# FPGA_PART1.net
KiCad netlist of a schematic drawn in Altium Designer
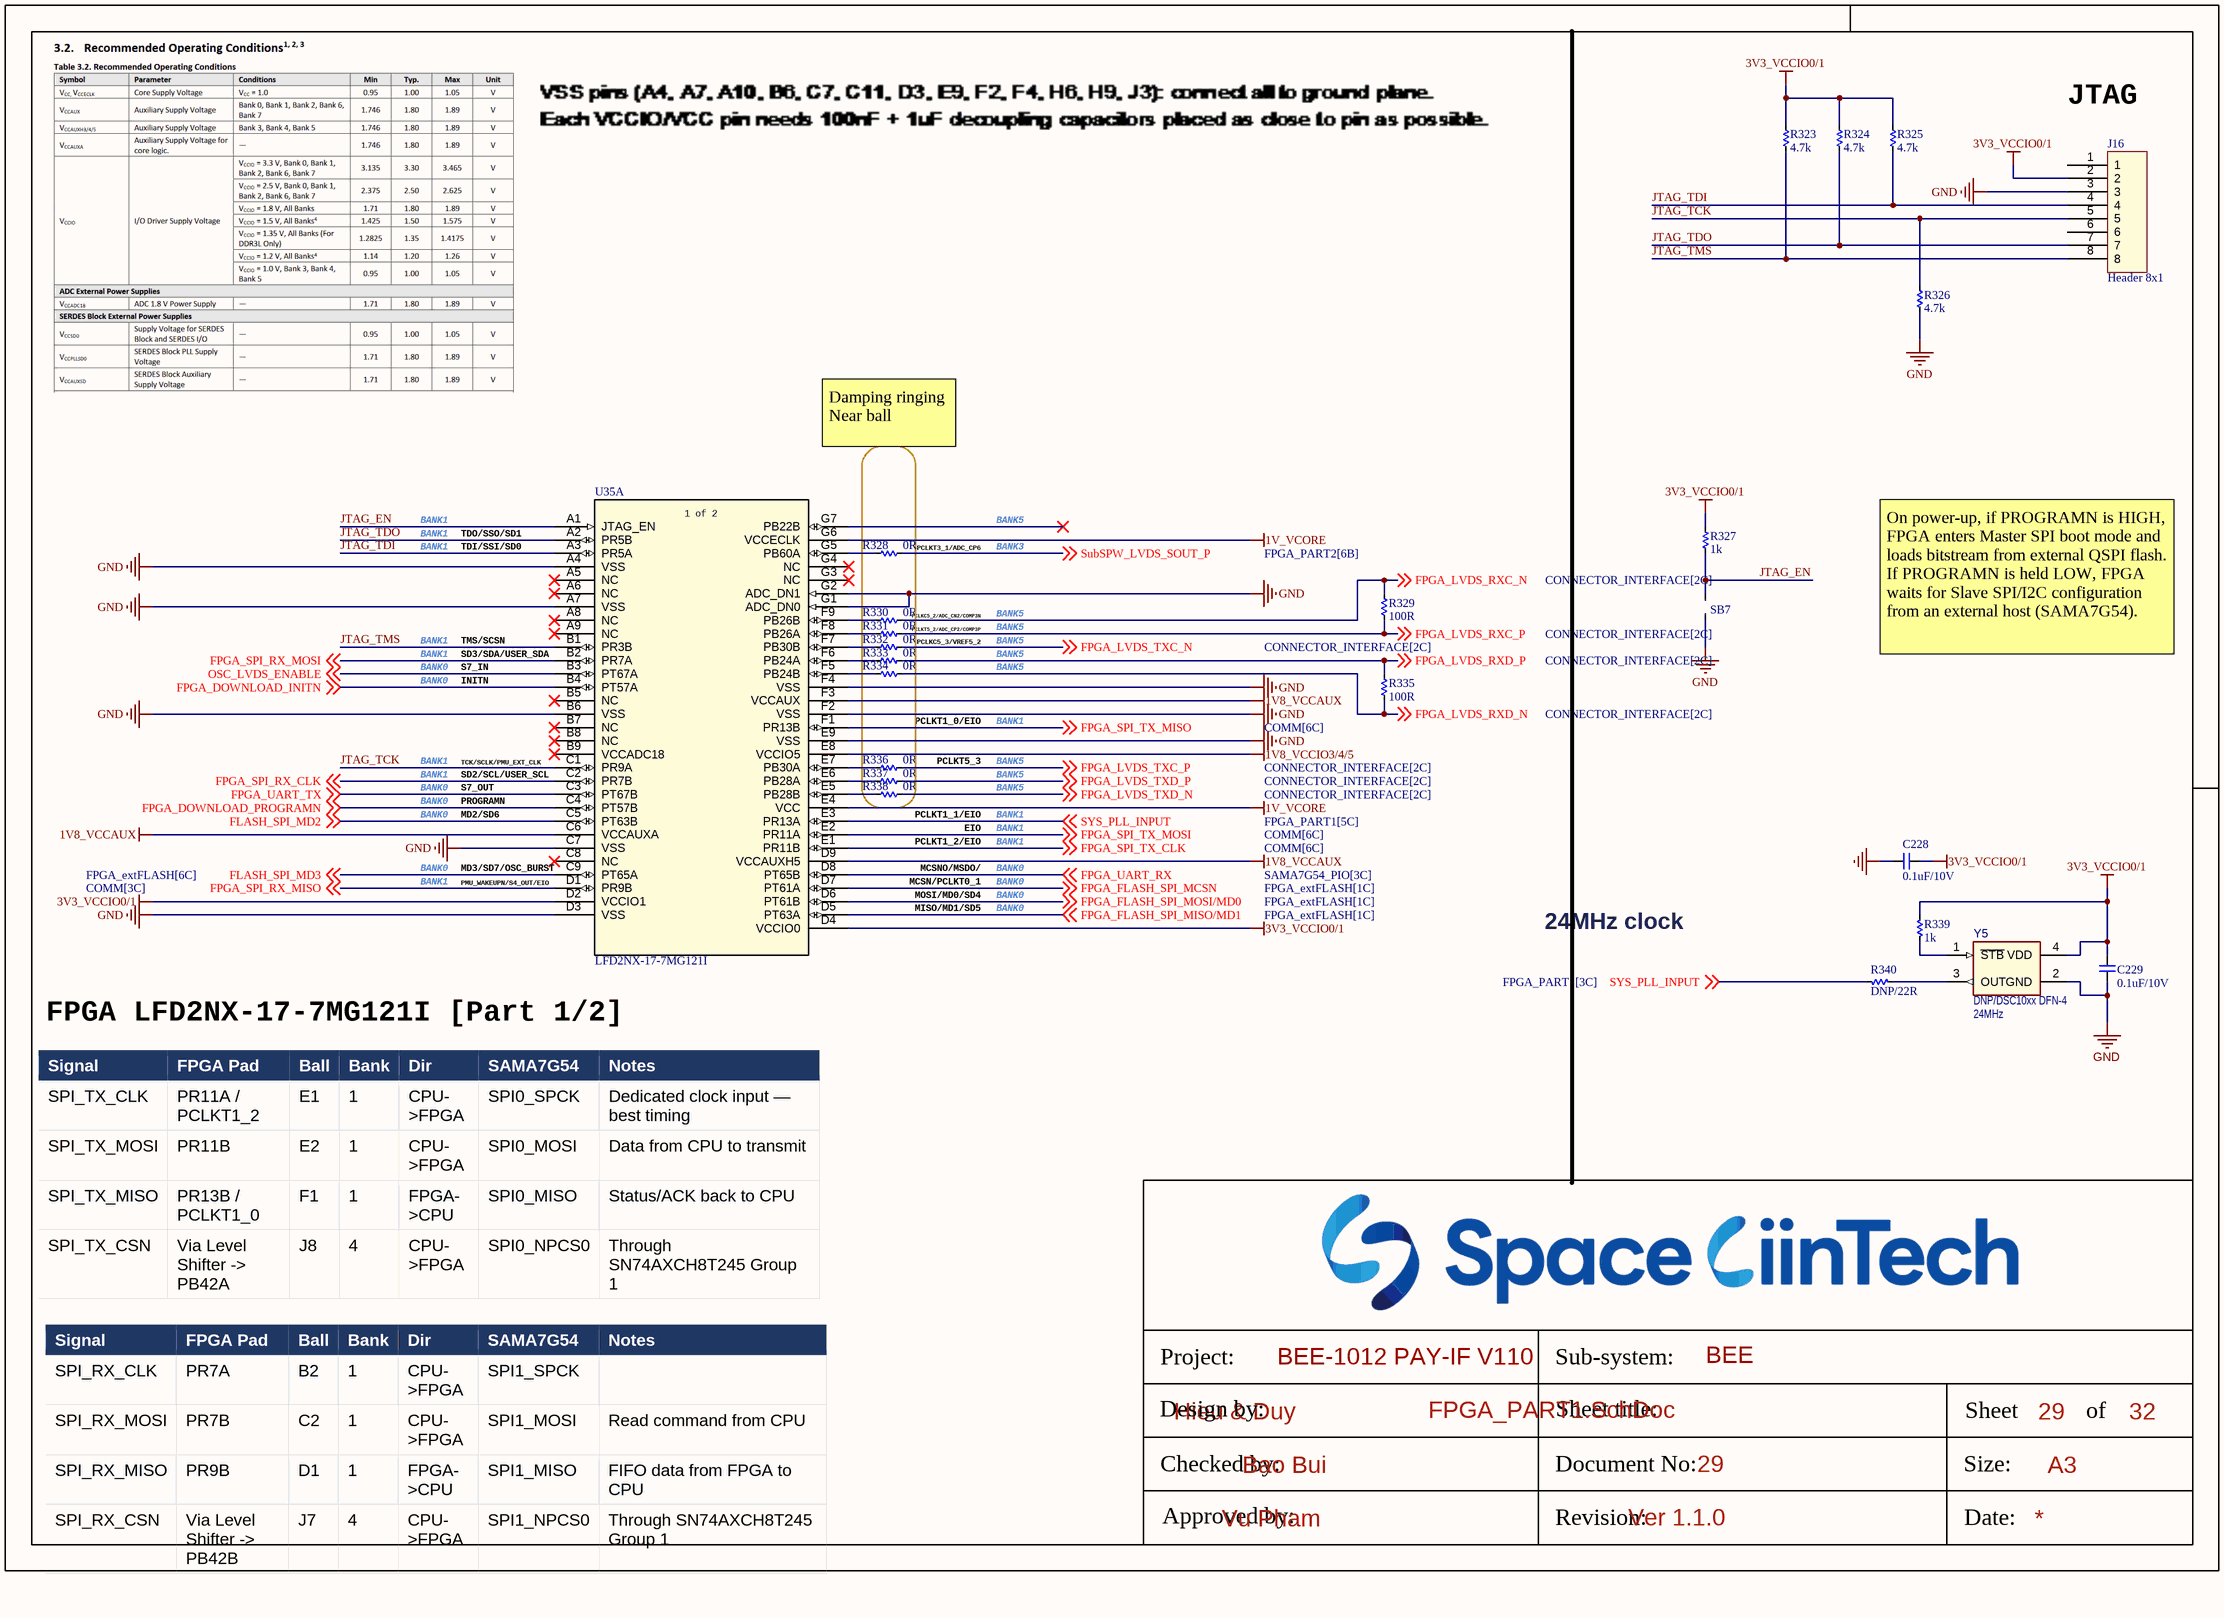
[diagram p0: FPGA_PART1.SchDoc]

(export (version "E")
  (design (tool "Eeschema 10.0.6"))
  (components
    (comp (ref "C228")
      (value "0.1uF/10V")
      (footprint "CAP_C_1005X50_L")
      (description "CAP")
      (libsource (lib "LABLIB") (part "_CAP_C_2"))
    )
    (comp (ref "C229")
      (value "0.1uF/10V")
      (footprint "CAP_C_1005X50_L")
      (description "CAP")
      (libsource (lib "LABLIB") (part "_CAP_C_2"))
    )
    (comp (ref "J16")
      (value "Header 8x1")
      (footprint "SAMTEC_TSM-108-01-L-SV-P-TR")
      (libsource (lib "LABLIB") (part "Header 8x1"))
    )
    (comp (ref "R323")
      (value "4.7k")
      (footprint "RES_C_1005x30_L")
      (description "RES")
      (libsource (lib "IFBschelib") (part "_RES_B_2"))
    )
    (comp (ref "R324")
      (value "4.7k")
      (footprint "RES_C_1005x30_L")
      (description "RES")
      (libsource (lib "IFBschelib") (part "_RES_B_2"))
    )
    (comp (ref "R325")
      (value "4.7k")
      (footprint "RES_C_1005x30_L")
      (description "RES")
      (libsource (lib "IFBschelib") (part "_RES_B_2"))
    )
    (comp (ref "R326")
      (value "4.7k")
      (footprint "RES_C_1005x30_L")
      (description "RES")
      (libsource (lib "IFBschelib") (part "_RES_B_2"))
    )
    (comp (ref "R327")
      (value "1k")
      (footprint "RES_C_1005x30_L")
      (description "RES")
      (libsource (lib "LABLIB") (part "_RES_B_2"))
    )
    (comp (ref "R328")
      (value "0R")
      (footprint "RES_C_1005x30_L")
      (description "RES")
      (libsource (lib "LABLIB") (part "_RES_B_2"))
    )
    (comp (ref "R329")
      (value "100R")
      (footprint "RES_C_1005x30_L")
      (description "RES")
      (libsource (lib "LABLIB") (part "_RES_B_2"))
    )
    (comp (ref "R330")
      (value "0R")
      (footprint "RES_C_1005x30_L")
      (description "RES")
      (libsource (lib "LABLIB") (part "_RES_B_2"))
    )
    (comp (ref "R331")
      (value "0R")
      (footprint "RES_C_1005x30_L")
      (description "RES")
      (libsource (lib "LABLIB") (part "_RES_B_2"))
    )
    (comp (ref "R332")
      (value "0R")
      (footprint "RES_C_1005x30_L")
      (description "RES")
      (libsource (lib "LABLIB") (part "_RES_B_2"))
    )
    (comp (ref "R333")
      (value "0R")
      (footprint "RES_C_1005x30_L")
      (description "RES")
      (libsource (lib "LABLIB") (part "_RES_B_2"))
    )
    (comp (ref "R334")
      (value "0R")
      (footprint "RES_C_1005x30_L")
      (description "RES")
      (libsource (lib "LABLIB") (part "_RES_B_2"))
    )
    (comp (ref "R335")
      (value "100R")
      (footprint "RES_C_1005x30_L")
      (description "RES")
      (libsource (lib "LABLIB") (part "_RES_B_2"))
    )
    (comp (ref "R336")
      (value "0R")
      (footprint "RES_C_1005x30_L")
      (description "RES")
      (libsource (lib "LABLIB") (part "_RES_B_2"))
    )
    (comp (ref "R337")
      (value "0R")
      (footprint "RES_C_1005x30_L")
      (description "RES")
      (libsource (lib "LABLIB") (part "_RES_B_2"))
    )
    (comp (ref "R338")
      (value "0R")
      (footprint "RES_C_1005x30_L")
      (description "RES")
      (libsource (lib "LABLIB") (part "_RES_B_2"))
    )
    (comp (ref "R339")
      (value "1k")
      (footprint "RES_C_1005x30_L")
      (description "RES")
      (libsource (lib "LABLIB") (part "_RES_B_2"))
    )
    (comp (ref "R340")
      (value "DNP/22R")
      (footprint "RES_C_1005x30_L")
      (description "RES")
      (libsource (lib "LABLIB") (part "_RES_B_2"))
    )
    (comp (ref "SB7")
      (value "JUMPER")
      (footprint "JUMPER_1608")
      (libsource (lib "IFBschelib") (part "JUMPER"))
    )
    (comp (ref "U35")
      (value "LFD2NX-17-7MG121I")
      (footprint "csfBGA121_LAT")
      (description "Description")
      (fields (field (name "COPYRIGHT") "Copyright (C) 2025 Ultra Librarian. All rights reserved."))
      (libsource (lib "IFBschelib_offline") (part "LFD2NX-17-7MG121I"))
    )
    (comp (ref "Y5")
      (value "DNP/DSC10xx DFN-4")
      (footprint "DFN-4_2.5x2")
      (fields (field (name "ALTIUM_VALUE") "24MHz") (field (name "OWNER") "Maurizio Gavardoni"))
      (libsource (lib "LABLIB") (part "DSC10xx DFN-4"))
    )
  )
  (nets
    (net (code "1") (name "/JTAG_EN") (class "Default")
      (node (ref "R327") (pin "1") (pinfunction "1_1") (pintype "passive"))
      (node (ref "SB7") (pin "2") (pinfunction "2_2") (pintype "passive"))
      (node (ref "U35") (pin "A1") (pinfunction "JTAG_EN_A1") (pintype "input"))
    )
    (net (code "2") (name "/JTAG_TCK") (class "Default")
      (node (ref "J16") (pin "5") (pinfunction "5_5") (pintype "passive"))
      (node (ref "R326") (pin "2") (pinfunction "2_2") (pintype "passive"))
      (node (ref "U35") (pin "C1") (pinfunction "PR9A_C1") (pintype "bidirectional"))
    )
    (net (code "3") (name "/JTAG_TDI") (class "Default")
      (node (ref "J16") (pin "4") (pinfunction "4_4") (pintype "passive"))
      (node (ref "R325") (pin "1") (pinfunction "1_1") (pintype "passive"))
      (node (ref "U35") (pin "A3") (pinfunction "PR5A_A3") (pintype "bidirectional"))
    )
    (net (code "4") (name "/JTAG_TDO") (class "Default")
      (node (ref "J16") (pin "7") (pinfunction "7_7") (pintype "passive"))
      (node (ref "R324") (pin "1") (pinfunction "1_1") (pintype "passive"))
      (node (ref "U35") (pin "A2") (pinfunction "PR5B_A2") (pintype "bidirectional"))
    )
    (net (code "5") (name "/JTAG_TMS") (class "Default")
      (node (ref "J16") (pin "8") (pinfunction "8_8") (pintype "passive"))
      (node (ref "R323") (pin "1") (pinfunction "1_1") (pintype "passive"))
      (node (ref "U35") (pin "B1") (pinfunction "PR3B_B1") (pintype "bidirectional"))
    )
    (net (code "6") (name "1V8_VCCAUX") (class "Default")
      (node (ref "U35") (pin "C6") (pinfunction "VCCAUXA_C6") (pintype "power_in"))
      (node (ref "U35") (pin "D9") (pinfunction "VCCAUXH5_D9") (pintype "power_in"))
      (node (ref "U35") (pin "F3") (pinfunction "VCCAUX_F3") (pintype "power_in"))
    )
    (net (code "7") (name "1V8_VCCIO3{slash}4{slash}5") (class "Default")
      (node (ref "U35") (pin "E8") (pinfunction "VCCIO5_E8") (pintype "power_in"))
    )
    (net (code "8") (name "1V_VCORE") (class "Default")
      (node (ref "U35") (pin "E4") (pinfunction "VCC_E4") (pintype "power_in"))
      (node (ref "U35") (pin "G6") (pinfunction "VCCECLK_G6") (pintype "power_in"))
    )
    (net (code "9") (name "3V3_VCCIO0{slash}1") (class "Default")
      (node (ref "C228") (pin "2") (pinfunction "2_2") (pintype "passive"))
      (node (ref "C229") (pin "2") (pinfunction "2_2") (pintype "passive"))
      (node (ref "J16") (pin "2") (pinfunction "2_2") (pintype "passive"))
      (node (ref "R323") (pin "2") (pinfunction "2_2") (pintype "passive"))
      (node (ref "R324") (pin "2") (pinfunction "2_2") (pintype "passive"))
      (node (ref "R325") (pin "2") (pinfunction "2_2") (pintype "passive"))
      (node (ref "R327") (pin "2") (pinfunction "2_2") (pintype "passive"))
      (node (ref "R339") (pin "2") (pinfunction "2_2") (pintype "passive"))
      (node (ref "U35") (pin "D2") (pinfunction "VCCIO1_D2") (pintype "power_in"))
      (node (ref "U35") (pin "D4") (pinfunction "VCCIO0_D4") (pintype "power_in"))
      (node (ref "Y5") (pin "4") (pinfunction "VDD_4") (pintype "power_in"))
    )
    (net (code "10") (name "FLASH_SPI_MD2") (class "Default")
      (node (ref "U35") (pin "C5") (pinfunction "PT63B_C5") (pintype "bidirectional"))
    )
    (net (code "11") (name "FLASH_SPI_MD3") (class "Default")
      (node (ref "U35") (pin "C9") (pinfunction "PT65A_C9") (pintype "bidirectional"))
    )
    (net (code "12") (name "FPGA_DOWNLOAD_INITN") (class "Default")
      (node (ref "U35") (pin "B4") (pinfunction "PT57A_B4") (pintype "bidirectional"))
    )
    (net (code "13") (name "FPGA_DOWNLOAD_PROGRAMN") (class "Default")
      (node (ref "U35") (pin "C4") (pinfunction "PT57B_C4") (pintype "bidirectional"))
    )
    (net (code "14") (name "FPGA_FLASH_SPI_MCSN") (class "Default")
      (node (ref "U35") (pin "D7") (pinfunction "PT61A_D7") (pintype "bidirectional"))
    )
    (net (code "15") (name "FPGA_FLASH_SPI_MISO{slash}MD1") (class "Default")
      (node (ref "U35") (pin "D5") (pinfunction "PT63A_D5") (pintype "bidirectional"))
    )
    (net (code "16") (name "FPGA_FLASH_SPI_MOSI{slash}MD0") (class "Default")
      (node (ref "U35") (pin "D6") (pinfunction "PT61B_D6") (pintype "bidirectional"))
    )
    (net (code "17") (name "FPGA_LVDS_RXC_N") (class "Default")
      (node (ref "R329") (pin "1") (pinfunction "1_1") (pintype "passive"))
      (node (ref "R330") (pin "1") (pinfunction "1_1") (pintype "passive"))
    )
    (net (code "18") (name "FPGA_LVDS_RXC_P") (class "Default")
      (node (ref "R329") (pin "2") (pinfunction "2_2") (pintype "passive"))
      (node (ref "R331") (pin "1") (pinfunction "1_1") (pintype "passive"))
    )
    (net (code "19") (name "FPGA_LVDS_RXD_N") (class "Default")
      (node (ref "R334") (pin "1") (pinfunction "1_1") (pintype "passive"))
      (node (ref "R335") (pin "2") (pinfunction "2_2") (pintype "passive"))
    )
    (net (code "20") (name "FPGA_LVDS_RXD_P") (class "Default")
      (node (ref "R333") (pin "1") (pinfunction "1_1") (pintype "passive"))
      (node (ref "R335") (pin "1") (pinfunction "1_1") (pintype "passive"))
    )
    (net (code "21") (name "FPGA_LVDS_TXC_N") (class "Default")
      (node (ref "R332") (pin "1") (pinfunction "1_1") (pintype "passive"))
    )
    (net (code "22") (name "FPGA_LVDS_TXC_P") (class "Default")
      (node (ref "R336") (pin "1") (pinfunction "1_1") (pintype "passive"))
    )
    (net (code "23") (name "FPGA_LVDS_TXD_N") (class "Default")
      (node (ref "R338") (pin "1") (pinfunction "1_1") (pintype "passive"))
    )
    (net (code "24") (name "FPGA_LVDS_TXD_P") (class "Default")
      (node (ref "R337") (pin "1") (pinfunction "1_1") (pintype "passive"))
    )
    (net (code "25") (name "FPGA_SPI_RX_CLK") (class "Default")
      (node (ref "U35") (pin "C2") (pinfunction "PR7B_C2") (pintype "bidirectional"))
    )
    (net (code "26") (name "FPGA_SPI_RX_MISO") (class "Default")
      (node (ref "U35") (pin "D1") (pinfunction "PR9B_D1") (pintype "bidirectional"))
    )
    (net (code "27") (name "FPGA_SPI_RX_MOSI") (class "Default")
      (node (ref "U35") (pin "B2") (pinfunction "PR7A_B2") (pintype "bidirectional"))
    )
    (net (code "28") (name "FPGA_SPI_TX_CLK") (class "Default")
      (node (ref "U35") (pin "E1") (pinfunction "PR11B_E1") (pintype "bidirectional"))
    )
    (net (code "29") (name "FPGA_SPI_TX_MISO") (class "Default")
      (node (ref "U35") (pin "F1") (pinfunction "PR13B_F1") (pintype "bidirectional"))
    )
    (net (code "30") (name "FPGA_SPI_TX_MOSI") (class "Default")
      (node (ref "U35") (pin "E2") (pinfunction "PR11A_E2") (pintype "bidirectional"))
    )
    (net (code "31") (name "FPGA_UART_RX") (class "Default")
      (node (ref "U35") (pin "D8") (pinfunction "PT65B_D8") (pintype "bidirectional"))
    )
    (net (code "32") (name "FPGA_UART_TX") (class "Default")
      (node (ref "U35") (pin "C3") (pinfunction "PT67B_C3") (pintype "bidirectional"))
    )
    (net (code "33") (name "GND") (class "Default")
      (node (ref "C228") (pin "1") (pinfunction "1_1") (pintype "passive"))
      (node (ref "C229") (pin "1") (pinfunction "1_1") (pintype "passive"))
      (node (ref "J16") (pin "3") (pinfunction "3_3") (pintype "passive"))
      (node (ref "R326") (pin "1") (pinfunction "1_1") (pintype "passive"))
      (node (ref "SB7") (pin "1") (pinfunction "1_1") (pintype "passive"))
      (node (ref "U35") (pin "A4") (pinfunction "VSS_A4") (pintype "power_in"))
      (node (ref "U35") (pin "A7") (pinfunction "VSS_A7") (pintype "power_in"))
      (node (ref "U35") (pin "B6") (pinfunction "VSS_B6") (pintype "power_in"))
      (node (ref "U35") (pin "C7") (pinfunction "VSS_C7") (pintype "power_in"))
      (node (ref "U35") (pin "D3") (pinfunction "VSS_D3") (pintype "power_in"))
      (node (ref "U35") (pin "E9") (pinfunction "VSS_E9") (pintype "power_in"))
      (node (ref "U35") (pin "F2") (pinfunction "VSS_F2") (pintype "power_in"))
      (node (ref "U35") (pin "F4") (pinfunction "VSS_F4") (pintype "power_in"))
      (node (ref "U35") (pin "G1") (pinfunction "ADC_DN0_G1") (pintype "input"))
      (node (ref "U35") (pin "G2") (pinfunction "ADC_DN1_G2") (pintype "input"))
      (node (ref "Y5") (pin "2") (pinfunction "GND_2") (pintype "power_in"))
    )
    (net (code "34") (name "Net-(U35A-PB24A)") (class "Default")
      (node (ref "R333") (pin "2") (pinfunction "2_2") (pintype "passive"))
      (node (ref "U35") (pin "F6") (pinfunction "PB24A_F6") (pintype "bidirectional"))
    )
    (net (code "35") (name "Net-(U35A-PB24B)") (class "Default")
      (node (ref "R334") (pin "2") (pinfunction "2_2") (pintype "passive"))
      (node (ref "U35") (pin "F5") (pinfunction "PB24B_F5") (pintype "bidirectional"))
    )
    (net (code "36") (name "Net-(U35A-PB26A)") (class "Default")
      (node (ref "R331") (pin "2") (pinfunction "2_2") (pintype "passive"))
      (node (ref "U35") (pin "F8") (pinfunction "PB26A_F8") (pintype "bidirectional"))
    )
    (net (code "37") (name "Net-(U35A-PB26B)") (class "Default")
      (node (ref "R330") (pin "2") (pinfunction "2_2") (pintype "passive"))
      (node (ref "U35") (pin "F9") (pinfunction "PB26B_F9") (pintype "bidirectional"))
    )
    (net (code "38") (name "Net-(U35A-PB28A)") (class "Default")
      (node (ref "R337") (pin "2") (pinfunction "2_2") (pintype "passive"))
      (node (ref "U35") (pin "E6") (pinfunction "PB28A_E6") (pintype "bidirectional"))
    )
    (net (code "39") (name "Net-(U35A-PB28B)") (class "Default")
      (node (ref "R338") (pin "2") (pinfunction "2_2") (pintype "passive"))
      (node (ref "U35") (pin "E5") (pinfunction "PB28B_E5") (pintype "bidirectional"))
    )
    (net (code "40") (name "Net-(U35A-PB30A)") (class "Default")
      (node (ref "R336") (pin "2") (pinfunction "2_2") (pintype "passive"))
      (node (ref "U35") (pin "E7") (pinfunction "PB30A_E7") (pintype "bidirectional"))
    )
    (net (code "41") (name "Net-(U35A-PB30B)") (class "Default")
      (node (ref "R332") (pin "2") (pinfunction "2_2") (pintype "passive"))
      (node (ref "U35") (pin "F7") (pinfunction "PB30B_F7") (pintype "bidirectional"))
    )
    (net (code "42") (name "Net-(U35A-PB60A)") (class "Default")
      (node (ref "R328") (pin "2") (pinfunction "2_2") (pintype "passive"))
      (node (ref "U35") (pin "G5") (pinfunction "PB60A_G5") (pintype "bidirectional"))
    )
    (net (code "43") (name "Net-(Y5-OUT)") (class "Default")
      (node (ref "R340") (pin "1") (pinfunction "1_1") (pintype "passive"))
      (node (ref "Y5") (pin "3") (pinfunction "OUT_3") (pintype "output"))
    )
    (net (code "44") (name "Net-(Y5-~{STB})") (class "Default")
      (node (ref "R339") (pin "1") (pinfunction "1_1") (pintype "passive"))
      (node (ref "Y5") (pin "1") (pinfunction "~{STB}_1") (pintype "input"))
    )
    (net (code "45") (name "OSC_LVDS_ENABLE") (class "Default")
      (node (ref "U35") (pin "B3") (pinfunction "PT67A_B3") (pintype "bidirectional"))
    )
    (net (code "46") (name "SYS_PLL_INPUT") (class "Default")
      (node (ref "R340") (pin "2") (pinfunction "2_2") (pintype "passive"))
      (node (ref "U35") (pin "E3") (pinfunction "PR13A_E3") (pintype "bidirectional"))
    )
    (net (code "47") (name "SubSPW_LVDS_SOUT_P") (class "Default")
      (node (ref "R328") (pin "1") (pinfunction "1_1") (pintype "passive"))
    )
    (net (code "48") (name "unconnected-(J16-Pad1)") (class "Default")
      (node (ref "J16") (pin "1") (pinfunction "1_1") (pintype "passive"))
    )
    (net (code "49") (name "unconnected-(J16-Pad6)") (class "Default")
      (node (ref "J16") (pin "6") (pinfunction "6_6") (pintype "passive"))
    )
    (net (code "50") (name "unconnected-(U35A-NC-PadA5)") (class "Default")
      (node (ref "U35") (pin "A5") (pinfunction "NC_A5") (pintype "passive+no_connect"))
    )
    (net (code "51") (name "unconnected-(U35A-NC-PadA6)") (class "Default")
      (node (ref "U35") (pin "A6") (pinfunction "NC_A6") (pintype "passive+no_connect"))
    )
    (net (code "52") (name "unconnected-(U35A-NC-PadA8)") (class "Default")
      (node (ref "U35") (pin "A8") (pinfunction "NC_A8") (pintype "passive+no_connect"))
    )
    (net (code "53") (name "unconnected-(U35A-NC-PadA9)") (class "Default")
      (node (ref "U35") (pin "A9") (pinfunction "NC_A9") (pintype "passive+no_connect"))
    )
    (net (code "54") (name "unconnected-(U35A-NC-PadB5)") (class "Default")
      (node (ref "U35") (pin "B5") (pinfunction "NC_B5") (pintype "passive+no_connect"))
    )
    (net (code "55") (name "unconnected-(U35A-NC-PadB7)") (class "Default")
      (node (ref "U35") (pin "B7") (pinfunction "NC_B7") (pintype "passive+no_connect"))
    )
    (net (code "56") (name "unconnected-(U35A-NC-PadB8)") (class "Default")
      (node (ref "U35") (pin "B8") (pinfunction "NC_B8") (pintype "passive+no_connect"))
    )
    (net (code "57") (name "unconnected-(U35A-NC-PadC8)") (class "Default")
      (node (ref "U35") (pin "C8") (pinfunction "NC_C8") (pintype "passive+no_connect"))
    )
    (net (code "58") (name "unconnected-(U35A-NC-PadG3)") (class "Default")
      (node (ref "U35") (pin "G3") (pinfunction "NC_G3") (pintype "passive+no_connect"))
    )
    (net (code "59") (name "unconnected-(U35A-NC-PadG4)") (class "Default")
      (node (ref "U35") (pin "G4") (pinfunction "NC_G4") (pintype "passive+no_connect"))
    )
    (net (code "60") (name "unconnected-(U35A-PB22B-PadG7)") (class "Default")
      (node (ref "U35") (pin "G7") (pinfunction "PB22B_G7") (pintype "bidirectional+no_connect"))
    )
    (net (code "61") (name "unconnected-(U35A-VCCADC18-PadB9)") (class "Default")
      (node (ref "U35") (pin "B9") (pinfunction "VCCADC18_B9") (pintype "power_in+no_connect"))
    )
  )
)
